# ss-test-rev1.net
KiCad netlist of a schematic drawn in EAGLE
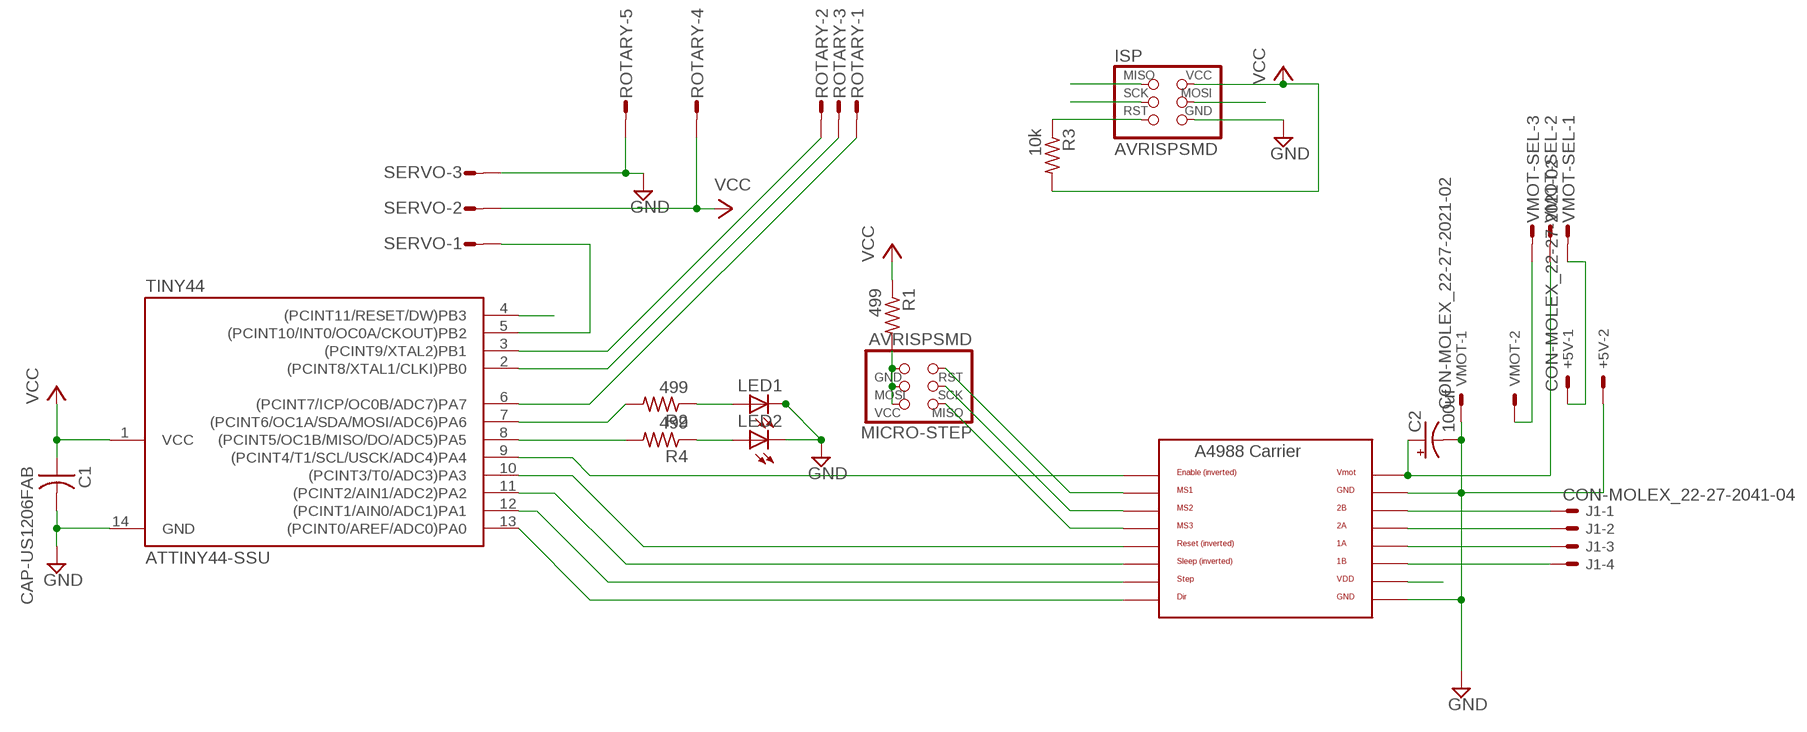
[diagram p0: schematic, sheet 1]

(export (version "E")
  (design (tool "Eeschema 10.0.6"))
  (components
    (comp (ref "+5V")
      (value "CON-MOLEX_22-27-2021-02")
      (footprint "eagle-import:CON-MOLEX_6410-02")
      (libsource (lib "eagle-import") (part "CON-MOLEX_22-?-0227-2021"))
    )
    (comp (ref "A4988")
      (value "REPRAPJR_A4988BREAKOUT")
      (footprint "eagle-import:REPRAPJR_A4988BREAKOUT")
      (libsource (lib "eagle-import") (part "REPRAPJR_A4988BREAKOUT"))
    )
    (comp (ref "C1")
      (value "CAP-US1206FAB")
      (footprint "eagle-import:C1206FAB")
      (libsource (lib "eagle-import") (part "CAP-US1206FAB"))
    )
    (comp (ref "C2")
      (value "100uf")
      (footprint "eagle-import:RCL_140CLH-0810")
      (libsource (lib "eagle-import") (part "RCL_CPOL-US140CLH-0810"))
    )
    (comp (ref "ISP")
      (value "AVRISPSMD")
      (footprint "eagle-import:2X03SMD")
      (libsource (lib "eagle-import") (part "AVRISPSMD"))
    )
    (comp (ref "J1")
      (value "CON-MOLEX_22-27-2041-04")
      (footprint "eagle-import:CON-MOLEX_6410-04")
      (libsource (lib "eagle-import") (part "CON-MOLEX_22-?-0427-2041"))
    )
    (comp (ref "LED1")
      (value "LED_LEDSML1206")
      (footprint "eagle-import:LED_SML1206")
      (libsource (lib "eagle-import") (part "LED_LEDSML1206"))
    )
    (comp (ref "LED2")
      (value "LED_LEDSML1206")
      (footprint "eagle-import:LED_SML1206")
      (libsource (lib "eagle-import") (part "LED_LEDSML1206"))
    )
    (comp (ref "MICRO-STEP")
      (value "AVRISPSMD")
      (footprint "eagle-import:2X03SMD")
      (libsource (lib "eagle-import") (part "AVRISPSMD"))
    )
    (comp (ref "R1")
      (value "499")
      (footprint "eagle-import:R1206FAB")
      (libsource (lib "eagle-import") (part "RES-US1206FAB"))
    )
    (comp (ref "R2")
      (value "499")
      (footprint "eagle-import:R1206FAB")
      (libsource (lib "eagle-import") (part "RES-US1206FAB"))
    )
    (comp (ref "R3")
      (value "10k")
      (footprint "eagle-import:R1206FAB")
      (libsource (lib "eagle-import") (part "RES-US1206FAB"))
    )
    (comp (ref "R4")
      (value "499")
      (footprint "eagle-import:R1206FAB")
      (libsource (lib "eagle-import") (part "RES-US1206FAB"))
    )
    (comp (ref "ROTARY")
      (value "S05P")
      (footprint "eagle-import:S05P")
      (libsource (lib "eagle-import") (part "S05P"))
    )
    (comp (ref "SERVO")
      (value "S03P")
      (footprint "eagle-import:S03P")
      (libsource (lib "eagle-import") (part "S03P"))
    )
    (comp (ref "TINY44")
      (value "ATTINY44-SSU")
      (footprint "eagle-import:SOIC14")
      (libsource (lib "eagle-import") (part "ATTINY44-SSU"))
    )
    (comp (ref "VMOT")
      (value "CON-MOLEX_22-27-2021-02")
      (footprint "eagle-import:CON-MOLEX_6410-02")
      (libsource (lib "eagle-import") (part "CON-MOLEX_22-?-0227-2021"))
    )
    (comp (ref "VMOT-SEL")
      (value "S03P")
      (footprint "eagle-import:S03P")
      (libsource (lib "eagle-import") (part "S03P"))
    )
  )
  (nets
    (net (code "1") (name "/MISO") (class "Default")
      (node (ref "ISP") (pin "1") (pinfunction "MISO_1") (pintype "passive"))
      (node (ref "R4") (pin "2") (pinfunction "2_2") (pintype "passive"))
      (node (ref "TINY44") (pin "8") (pinfunction "(PCINT5/OC1B/MISO/DO/ADC5)PA5_8") (pintype "bidirectional"))
    )
    (net (code "2") (name "/MOSI") (class "Default")
      (node (ref "ISP") (pin "4") (pinfunction "MOSI_4") (pintype "passive"))
      (node (ref "R2") (pin "2") (pinfunction "2_2") (pintype "passive"))
      (node (ref "TINY44") (pin "7") (pinfunction "(PCINT6/OC1A/SDA/MOSI/ADC6)PA6_7") (pintype "bidirectional"))
    )
    (net (code "3") (name "/RST") (class "Default")
      (node (ref "ISP") (pin "5") (pinfunction "RST_5") (pintype "passive"))
      (node (ref "R3") (pin "1") (pinfunction "1_1") (pintype "passive"))
      (node (ref "TINY44") (pin "4") (pinfunction "(PCINT11/RESET/DW)PB3_4") (pintype "bidirectional"))
    )
    (net (code "4") (name "/SCK") (class "Default")
      (node (ref "A4988") (pin "EN") (pinfunction "EN_EN") (pintype "input"))
      (node (ref "ISP") (pin "3") (pinfunction "SCK_3") (pintype "passive"))
      (node (ref "TINY44") (pin "9") (pinfunction "(PCINT4/T1/SCL/USCK/ADC4)PA4_9") (pintype "bidirectional"))
    )
    (net (code "5") (name "GND") (class "Default")
      (node (ref "+5V") (pin "2") (pinfunction "S_2") (pintype "passive"))
      (node (ref "A4988") (pin "GND") (pinfunction "GND_GND") (pintype "power_in"))
      (node (ref "A4988") (pin "GND@0") (pinfunction "GND_GND@0") (pintype "power_in"))
      (node (ref "C1") (pin "2") (pinfunction "2_2") (pintype "passive"))
      (node (ref "C2") (pin "-") (pinfunction "-_-") (pintype "passive"))
      (node (ref "ISP") (pin "6") (pinfunction "GND_6") (pintype "passive"))
      (node (ref "LED1") (pin "C") (pinfunction "C_C") (pintype "passive"))
      (node (ref "LED2") (pin "C") (pinfunction "C_C") (pintype "passive"))
      (node (ref "ROTARY") (pin "5") (pinfunction "S_5") (pintype "passive"))
      (node (ref "SERVO") (pin "3") (pinfunction "S_3") (pintype "passive"))
      (node (ref "TINY44") (pin "14") (pinfunction "GND_14") (pintype "power_in"))
      (node (ref "VMOT") (pin "1") (pinfunction "S_1") (pintype "passive"))
    )
    (net (code "6") (name "Net-(A4988-SLEEP)") (class "Default")
      (node (ref "A4988") (pin "SLP") (pinfunction "SLEEP_SLP") (pintype "input"))
      (node (ref "TINY44") (pin "11") (pinfunction "(PCINT2/AIN1/ADC2)PA2_11") (pintype "bidirectional"))
    )
    (net (code "7") (name "Net-(J1A-S)") (class "Default")
      (node (ref "A4988") (pin "2B") (pinfunction "2B_2B") (pintype "output"))
      (node (ref "J1") (pin "1") (pinfunction "S_1") (pintype "passive"))
    )
    (net (code "8") (name "Net-(J1B-S)") (class "Default")
      (node (ref "A4988") (pin "2A") (pinfunction "2A_2A") (pintype "output"))
      (node (ref "J1") (pin "2") (pinfunction "S_2") (pintype "passive"))
    )
    (net (code "9") (name "Net-(J1C-S)") (class "Default")
      (node (ref "A4988") (pin "1A") (pinfunction "1A_1A") (pintype "output"))
      (node (ref "J1") (pin "3") (pinfunction "S_3") (pintype "passive"))
    )
    (net (code "10") (name "Net-(J1D-S)") (class "Default")
      (node (ref "A4988") (pin "1B") (pinfunction "1B_1B") (pintype "output"))
      (node (ref "J1") (pin "4") (pinfunction "S_4") (pintype "passive"))
    )
    (net (code "11") (name "Net-(LED1-PadA)") (class "Default")
      (node (ref "LED1") (pin "A") (pinfunction "A_A") (pintype "passive"))
      (node (ref "R2") (pin "1") (pinfunction "1_1") (pintype "passive"))
    )
    (net (code "12") (name "Net-(LED2-PadA)") (class "Default")
      (node (ref "LED2") (pin "A") (pinfunction "A_A") (pintype "passive"))
      (node (ref "R4") (pin "1") (pinfunction "1_1") (pintype "passive"))
    )
    (net (code "13") (name "Net-(MICRO-STEP-GND)") (class "Default")
      (node (ref "MICRO-STEP") (pin "2") (pinfunction "VCC_2") (pintype "passive"))
      (node (ref "MICRO-STEP") (pin "4") (pinfunction "MOSI_4") (pintype "passive"))
      (node (ref "MICRO-STEP") (pin "6") (pinfunction "GND_6") (pintype "passive"))
      (node (ref "R1") (pin "2") (pinfunction "2_2") (pintype "passive"))
    )
    (net (code "14") (name "Net-(MICRO-STEP-MISO)") (class "Default")
      (node (ref "A4988") (pin "MS3") (pinfunction "MS3_MS3") (pintype "input"))
      (node (ref "MICRO-STEP") (pin "1") (pinfunction "MISO_1") (pintype "passive"))
    )
    (net (code "15") (name "Net-(MICRO-STEP-RST)") (class "Default")
      (node (ref "A4988") (pin "MS1") (pinfunction "MS1_MS1") (pintype "input"))
      (node (ref "MICRO-STEP") (pin "5") (pinfunction "RST_5") (pintype "passive"))
    )
    (net (code "16") (name "Net-(MICRO-STEP-SCK)") (class "Default")
      (node (ref "A4988") (pin "MS2") (pinfunction "MS2_MS2") (pintype "input"))
      (node (ref "MICRO-STEP") (pin "3") (pinfunction "SCK_3") (pintype "passive"))
    )
    (net (code "17") (name "Net-(ROTARYA-S)") (class "Default")
      (node (ref "ROTARY") (pin "1") (pinfunction "S_1") (pintype "passive"))
      (node (ref "TINY44") (pin "6") (pinfunction "(PCINT7/ICP/OC0B/ADC7)PA7_6") (pintype "bidirectional"))
    )
    (net (code "18") (name "Net-(ROTARYB-S)") (class "Default")
      (node (ref "ROTARY") (pin "2") (pinfunction "S_2") (pintype "passive"))
      (node (ref "TINY44") (pin "3") (pinfunction "(PCINT9/XTAL2)PB1_3") (pintype "bidirectional"))
    )
    (net (code "19") (name "Net-(ROTARYC-S)") (class "Default")
      (node (ref "ROTARY") (pin "3") (pinfunction "S_3") (pintype "passive"))
      (node (ref "TINY44") (pin "2") (pinfunction "(PCINT8/XTAL1/CLKI)PB0_2") (pintype "bidirectional"))
    )
    (net (code "20") (name "Net-(SERVOA-S)") (class "Default")
      (node (ref "SERVO") (pin "1") (pinfunction "S_1") (pintype "passive"))
      (node (ref "TINY44") (pin "5") (pinfunction "(PCINT10/INT0/OC0A/CKOUT)PB2_5") (pintype "bidirectional"))
    )
    (net (code "21") (name "Net-(TINY44-(PCINT0{slash}AREF{slash}ADC0)PA0)") (class "Default")
      (node (ref "A4988") (pin "DIR") (pinfunction "DIR_DIR") (pintype "input"))
      (node (ref "TINY44") (pin "13") (pinfunction "(PCINT0/AREF/ADC0)PA0_13") (pintype "bidirectional"))
    )
    (net (code "22") (name "Net-(TINY44-(PCINT1{slash}AIN0{slash}ADC1)PA1)") (class "Default")
      (node (ref "A4988") (pin "STEP") (pinfunction "STEP_STEP") (pintype "input"))
      (node (ref "TINY44") (pin "12") (pinfunction "(PCINT1/AIN0/ADC1)PA1_12") (pintype "bidirectional"))
    )
    (net (code "23") (name "Net-(TINY44-(PCINT3{slash}T0{slash}ADC3)PA3)") (class "Default")
      (node (ref "A4988") (pin "RST") (pinfunction "RST_RST") (pintype "input"))
      (node (ref "TINY44") (pin "10") (pinfunction "(PCINT3/T0/ADC3)PA3_10") (pintype "bidirectional"))
    )
    (net (code "24") (name "Net-(VMOT-SELB-S)") (class "Default")
      (node (ref "A4988") (pin "VMOT") (pinfunction "VMOT_VMOT") (pintype "power_in"))
      (node (ref "C2") (pin "+") (pinfunction "+_+") (pintype "passive"))
      (node (ref "VMOT-SEL") (pin "2") (pinfunction "S_2") (pintype "passive"))
    )
    (net (code "25") (name "Net-(VMOT-SELC-S)") (class "Default")
      (node (ref "VMOT") (pin "2") (pinfunction "S_2") (pintype "passive"))
      (node (ref "VMOT-SEL") (pin "3") (pinfunction "S_3") (pintype "passive"))
    )
    (net (code "26") (name "VCC") (class "Default")
      (node (ref "+5V") (pin "1") (pinfunction "S_1") (pintype "passive"))
      (node (ref "A4988") (pin "VDD") (pinfunction "VDD_VDD") (pintype "power_in"))
      (node (ref "C1") (pin "1") (pinfunction "1_1") (pintype "passive"))
      (node (ref "ISP") (pin "2") (pinfunction "VCC_2") (pintype "passive"))
      (node (ref "R1") (pin "1") (pinfunction "1_1") (pintype "passive"))
      (node (ref "R3") (pin "2") (pinfunction "2_2") (pintype "passive"))
      (node (ref "ROTARY") (pin "4") (pinfunction "S_4") (pintype "passive"))
      (node (ref "SERVO") (pin "2") (pinfunction "S_2") (pintype "passive"))
      (node (ref "TINY44") (pin "1") (pinfunction "VCC_1") (pintype "power_in"))
      (node (ref "VMOT-SEL") (pin "1") (pinfunction "S_1") (pintype "passive"))
    )
  )
)
